# 02-ESP32.net
KiCad netlist of a schematic drawn in Altium Designer
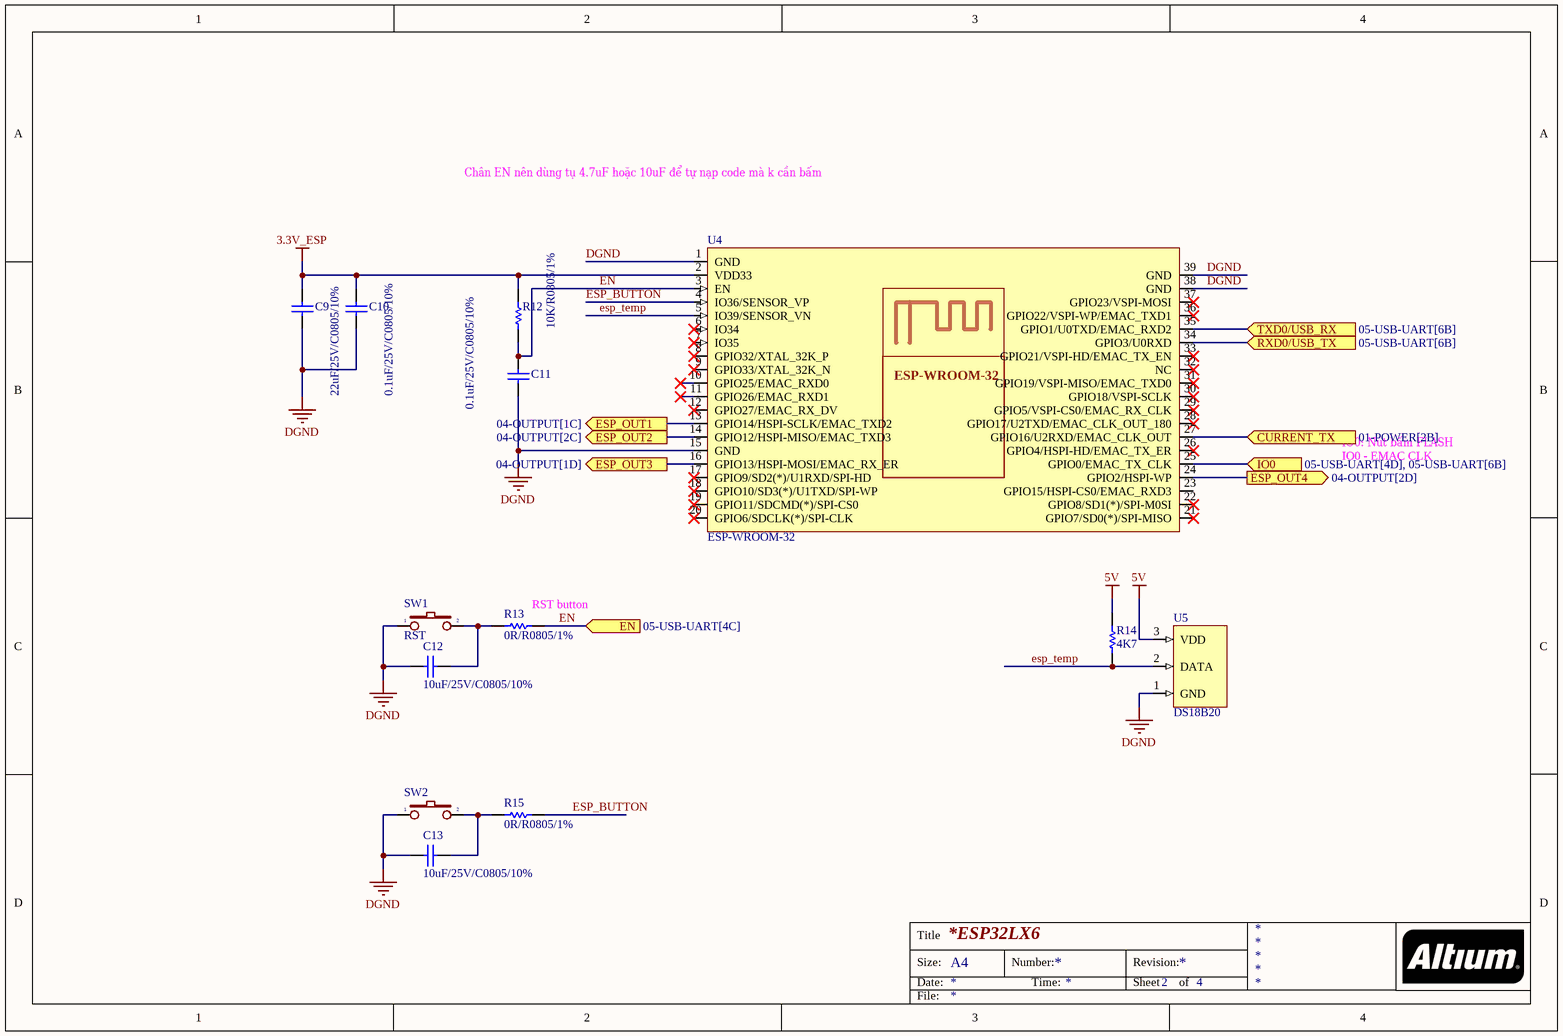
[diagram p0: 02-ESP32.SchDoc]

(export (version "E")
  (design (tool "Eeschema 10.0.6"))
  (components
    (comp (ref "C9")
      (value "22uF/25V/C0805/10%")
      (footprint "CAP_CERA_C2012(CC0805INCH)")
      (description "22µF ±20% 25V Ceramic Capacitor X5R 0805 (2012 Metric)")
      (fields (field (name "MANUFACTURER") "Tariff Applied"))
      (libsource (lib "GSHT_181013") (part "0.1uF/50V/C0603/10%"))
    )
    (comp (ref "C10")
      (value "0.1uF/25V/C0805/10%")
      (footprint "CAP_CERA_C2012(CC0805INCH)")
      (description "0.1µF ±10% 25V Ceramic Capacitor X7R 0805 (2012 Metric)")
      (libsource (lib "GSHT_181013") (part "0.1uF/50V/C0603/10%"))
    )
    (comp (ref "C11")
      (value "0.1uF/25V/C0805/10%")
      (footprint "CAP_CERA_C2012(CC0805INCH)")
      (description "0.1µF ±10% 25V Ceramic Capacitor X7R 0805 (2012 Metric)")
      (libsource (lib "GSHT_181013") (part "0.1uF/50V/C0603/10%"))
    )
    (comp (ref "C12")
      (value "10uF/25V/C0805/10%")
      (footprint "CAP_CERA_C2012(CC0805INCH)")
      (description "0.1µF ±10% 25V Ceramic Capacitor X7R 0805 (2012 Metric)")
      (libsource (lib "GSHT_181013") (part "0.1uF/50V/C0603/10%"))
    )
    (comp (ref "C13")
      (value "10uF/25V/C0805/10%")
      (footprint "CAP_CERA_C2012(CC0805INCH)")
      (description "0.1µF ±10% 25V Ceramic Capacitor X7R 0805 (2012 Metric)")
      (libsource (lib "GSHT_181013") (part "0.1uF/50V/C0603/10%"))
    )
    (comp (ref "R12")
      (value "10K/R0805/1%")
      (footprint "Res 0805 SMD")
      (description "10 kOhms ±1% 0.125W, 1/8W Chip Resistor 0805 (2012 Metric) Thick Film")
      (libsource (lib "GSHT_181013") (part "200K/R0603/1%"))
    )
    (comp (ref "R13")
      (value "0R/R0805/1%")
      (footprint "Res 0805 SMD")
      (description "0 Ohms Jumper 0.125W, 1/8W Chip Resistor 0805 (2012 Metric) Automotive AEC-Q200 Thick Film")
      (libsource (lib "GSHT_181013") (part "200K/R0603/1%"))
    )
    (comp (ref "R14")
      (value "4K7")
      (footprint "Res 0805 SMD")
      (description "4k7 Ohms Jumper 0.125W, 1/8W Chip Resistor 0805 (2012 Metric)")
      (libsource (lib "GSHT_181013") (part "200K/R0603/1%"))
    )
    (comp (ref "R15")
      (value "0R/R0805/1%")
      (footprint "Res 0805 SMD")
      (description "0 Ohms Jumper 0.125W, 1/8W Chip Resistor 0805 (2012 Metric) Automotive AEC-Q200 Thick Film")
      (libsource (lib "GSHT_181013") (part "200K/R0603/1%"))
    )
    (comp (ref "SW1")
      (value "RST")
      (footprint "Button 3x4mm")
      (description "SWITCH TACTILE SPST-NO 0.05A 12V")
      (libsource (lib "lpson") (part "SW2"))
    )
    (comp (ref "SW2")
      (value "RST")
      (footprint "Button 3x4mm")
      (description "SWITCH TACTILE SPST-NO 0.05A 12V")
      (libsource (lib "lpson") (part "SW2"))
    )
    (comp (ref "U4")
      (value "ESP-WROOM-32")
      (footprint "ESP32 WROOM")
      (description "ESP-WROOM-32 (8MB), WIFI MODULE 64 MBITS SPI FLASH")
      (libsource (lib "lpson") (part "ESP-WROOM-32"))
    )
    (comp (ref "U5") (value "DS18B20") (footprint "P2N2222AG") (libsource (lib "Schlib1") (part "DS18B20")))
  )
  (nets
    (net (code "1") (name "/CURRENT_TX") (class "Default")
      (node (ref "U4") (pin "27") (pinfunction "GPIO16/U2RXD/EMAC_CLK_OUT_27") (pintype "passive"))
    )
    (net (code "2") (name "/EN") (class "Default")
      (node (ref "C11") (pin "2") (pinfunction "2_2") (pintype "passive"))
      (node (ref "R12") (pin "2") (pinfunction "2_2") (pintype "passive"))
      (node (ref "R13") (pin "2") (pinfunction "2_2") (pintype "passive"))
      (node (ref "U4") (pin "3") (pinfunction "EN_3") (pintype "input"))
    )
    (net (code "3") (name "/ESP_BUTTON") (class "Default")
      (node (ref "R15") (pin "2") (pinfunction "2_2") (pintype "passive"))
      (node (ref "U4") (pin "4") (pinfunction "IO36/SENSOR_VP_4") (pintype "input"))
    )
    (net (code "4") (name "/ESP_OUT1") (class "Default")
      (node (ref "U4") (pin "13") (pinfunction "GPIO14/HSPI-SCLK/EMAC_TXD2_13") (pintype "passive"))
    )
    (net (code "5") (name "/ESP_OUT2") (class "Default")
      (node (ref "U4") (pin "14") (pinfunction "GPIO12/HSPI-MISO/EMAC_TXD3_14") (pintype "passive"))
    )
    (net (code "6") (name "/ESP_OUT3") (class "Default")
      (node (ref "U4") (pin "16") (pinfunction "GPIO13/HSPI-MOSI/EMAC_RX_ER_16") (pintype "passive"))
    )
    (net (code "7") (name "/ESP_OUT4") (class "Default")
      (node (ref "U4") (pin "24") (pinfunction "GPIO2/HSPI-WP_24") (pintype "passive"))
    )
    (net (code "8") (name "/IO0") (class "Default")
      (node (ref "U4") (pin "25") (pinfunction "GPIO0/EMAC_TX_CLK_25") (pintype "passive"))
    )
    (net (code "9") (name "/RXD0{slash}USB_TX") (class "Default")
      (node (ref "U4") (pin "34") (pinfunction "GPIO3/U0RXD_34") (pintype "passive"))
    )
    (net (code "10") (name "/TXD0{slash}USB_RX") (class "Default")
      (node (ref "U4") (pin "35") (pinfunction "GPIO1/U0TXD/EMAC_RXD2_35") (pintype "passive"))
    )
    (net (code "11") (name "/esp_temp") (class "Default")
      (node (ref "R14") (pin "1") (pinfunction "1_1") (pintype "passive"))
      (node (ref "U4") (pin "5") (pinfunction "IO39/SENSOR_VN_5") (pintype "input"))
      (node (ref "U5") (pin "2") (pinfunction "DATA_2") (pintype "input"))
    )
    (net (code "12") (name "3.3V_ESP") (class "Default")
      (node (ref "C10") (pin "2") (pinfunction "2_2") (pintype "passive"))
      (node (ref "C9") (pin "2") (pinfunction "2_2") (pintype "passive"))
      (node (ref "R12") (pin "1") (pinfunction "1_1") (pintype "passive"))
      (node (ref "U4") (pin "2") (pinfunction "VDD33_2") (pintype "passive"))
    )
    (net (code "13") (name "5V") (class "Default")
      (node (ref "R14") (pin "2") (pinfunction "2_2") (pintype "passive"))
      (node (ref "U5") (pin "3") (pinfunction "VDD_3") (pintype "input"))
    )
    (net (code "14") (name "DGND") (class "Default")
      (node (ref "C10") (pin "1") (pinfunction "1_1") (pintype "passive"))
      (node (ref "C11") (pin "1") (pinfunction "1_1") (pintype "passive"))
      (node (ref "C12") (pin "2") (pinfunction "2_2") (pintype "passive"))
      (node (ref "C13") (pin "2") (pinfunction "2_2") (pintype "passive"))
      (node (ref "C9") (pin "1") (pinfunction "1_1") (pintype "passive"))
      (node (ref "SW1") (pin "1") (pinfunction "1_1") (pintype "passive"))
      (node (ref "SW2") (pin "1") (pinfunction "1_1") (pintype "passive"))
      (node (ref "U4") (pin "1") (pinfunction "GND_1") (pintype "passive"))
      (node (ref "U4") (pin "15") (pinfunction "GND_15") (pintype "passive"))
      (node (ref "U4") (pin "38") (pinfunction "GND_38") (pintype "passive"))
      (node (ref "U4") (pin "39") (pinfunction "GND_39") (pintype "passive"))
      (node (ref "U5") (pin "1") (pinfunction "GND_1") (pintype "input"))
    )
    (net (code "15") (name "Net-(C12-Pad1)") (class "Default")
      (node (ref "C12") (pin "1") (pinfunction "1_1") (pintype "passive"))
      (node (ref "R13") (pin "1") (pinfunction "1_1") (pintype "passive"))
      (node (ref "SW1") (pin "2") (pinfunction "2_2") (pintype "passive"))
    )
    (net (code "16") (name "Net-(C13-Pad1)") (class "Default")
      (node (ref "C13") (pin "1") (pinfunction "1_1") (pintype "passive"))
      (node (ref "R15") (pin "1") (pinfunction "1_1") (pintype "passive"))
      (node (ref "SW2") (pin "2") (pinfunction "2_2") (pintype "passive"))
    )
    (net (code "17") (name "unconnected-(U4-GPIO4{slash}HSPI-HD{slash}EMAC_TX_ER-Pad26)") (class "Default")
      (node (ref "U4") (pin "26") (pinfunction "GPIO4/HSPI-HD/EMAC_TX_ER_26") (pintype "passive+no_connect"))
    )
    (net (code "18") (name "unconnected-(U4-GPIO5{slash}VSPI-CS0{slash}EMAC_RX_CLK-Pad29)") (class "Default")
      (node (ref "U4") (pin "29") (pinfunction "GPIO5/VSPI-CS0/EMAC_RX_CLK_29") (pintype "passive+no_connect"))
    )
    (net (code "19") (name "unconnected-(U4-GPIO6{slash}SDCLK(*){slash}SPI-CLK-Pad20)") (class "Default")
      (node (ref "U4") (pin "20") (pinfunction "GPIO6/SDCLK(*)/SPI-CLK_20") (pintype "passive+no_connect"))
    )
    (net (code "20") (name "unconnected-(U4-GPIO7{slash}SD0(*){slash}SPI-MISO-Pad21)") (class "Default")
      (node (ref "U4") (pin "21") (pinfunction "GPIO7/SD0(*)/SPI-MISO_21") (pintype "passive+no_connect"))
    )
    (net (code "21") (name "unconnected-(U4-GPIO8{slash}SD1(*){slash}SPI-M0SI-Pad22)") (class "Default")
      (node (ref "U4") (pin "22") (pinfunction "GPIO8/SD1(*)/SPI-M0SI_22") (pintype "passive+no_connect"))
    )
    (net (code "22") (name "unconnected-(U4-GPIO9{slash}SD2(*){slash}U1RXD{slash}SPI-HD-Pad17)") (class "Default")
      (node (ref "U4") (pin "17") (pinfunction "GPIO9/SD2(*)/U1RXD/SPI-HD_17") (pintype "passive+no_connect"))
    )
    (net (code "23") (name "unconnected-(U4-GPIO10{slash}SD3(*){slash}U1TXD{slash}SPI-WP-Pad18)") (class "Default")
      (node (ref "U4") (pin "18") (pinfunction "GPIO10/SD3(*)/U1TXD/SPI-WP_18") (pintype "passive+no_connect"))
    )
    (net (code "24") (name "unconnected-(U4-GPIO11{slash}SDCMD(*){slash}SPI-CS0-Pad19)") (class "Default")
      (node (ref "U4") (pin "19") (pinfunction "GPIO11/SDCMD(*)/SPI-CS0_19") (pintype "passive+no_connect"))
    )
    (net (code "25") (name "unconnected-(U4-GPIO15{slash}HSPI-CS0{slash}EMAC_RXD3-Pad23)") (class "Default")
      (node (ref "U4") (pin "23") (pinfunction "GPIO15/HSPI-CS0/EMAC_RXD3_23") (pintype "passive"))
    )
    (net (code "26") (name "unconnected-(U4-GPIO17{slash}U2TXD{slash}EMAC_CLK_OUT_180-Pad28)") (class "Default")
      (node (ref "U4") (pin "28") (pinfunction "GPIO17/U2TXD/EMAC_CLK_OUT_180_28") (pintype "passive+no_connect"))
    )
    (net (code "27") (name "unconnected-(U4-GPIO18{slash}VSPI-SCLK-Pad30)") (class "Default")
      (node (ref "U4") (pin "30") (pinfunction "GPIO18/VSPI-SCLK_30") (pintype "passive+no_connect"))
    )
    (net (code "28") (name "unconnected-(U4-GPIO19{slash}VSPI-MISO{slash}EMAC_TXD0-Pad31)") (class "Default")
      (node (ref "U4") (pin "31") (pinfunction "GPIO19/VSPI-MISO/EMAC_TXD0_31") (pintype "passive+no_connect"))
    )
    (net (code "29") (name "unconnected-(U4-GPIO21{slash}VSPI-HD{slash}EMAC_TX_EN-Pad33)") (class "Default")
      (node (ref "U4") (pin "33") (pinfunction "GPIO21/VSPI-HD/EMAC_TX_EN_33") (pintype "passive+no_connect"))
    )
    (net (code "30") (name "unconnected-(U4-GPIO22{slash}VSPI-WP{slash}EMAC_TXD1-Pad36)") (class "Default")
      (node (ref "U4") (pin "36") (pinfunction "GPIO22/VSPI-WP/EMAC_TXD1_36") (pintype "passive+no_connect"))
    )
    (net (code "31") (name "unconnected-(U4-GPIO23{slash}VSPI-MOSI-Pad37)") (class "Default")
      (node (ref "U4") (pin "37") (pinfunction "GPIO23/VSPI-MOSI_37") (pintype "passive+no_connect"))
    )
    (net (code "32") (name "unconnected-(U4-GPIO25{slash}EMAC_RXD0-Pad10)") (class "Default")
      (node (ref "U4") (pin "10") (pinfunction "GPIO25/EMAC_RXD0_10") (pintype "passive+no_connect"))
    )
    (net (code "33") (name "unconnected-(U4-GPIO26{slash}EMAC_RXD1-Pad11)") (class "Default")
      (node (ref "U4") (pin "11") (pinfunction "GPIO26/EMAC_RXD1_11") (pintype "passive+no_connect"))
    )
    (net (code "34") (name "unconnected-(U4-GPIO27{slash}EMAC_RX_DV-Pad12)") (class "Default")
      (node (ref "U4") (pin "12") (pinfunction "GPIO27/EMAC_RX_DV_12") (pintype "passive+no_connect"))
    )
    (net (code "35") (name "unconnected-(U4-GPIO32{slash}XTAL_32K_P-Pad8)") (class "Default")
      (node (ref "U4") (pin "8") (pinfunction "GPIO32/XTAL_32K_P_8") (pintype "passive+no_connect"))
    )
    (net (code "36") (name "unconnected-(U4-GPIO33{slash}XTAL_32K_N-Pad9)") (class "Default")
      (node (ref "U4") (pin "9") (pinfunction "GPIO33/XTAL_32K_N_9") (pintype "passive+no_connect"))
    )
    (net (code "37") (name "unconnected-(U4-IO34-Pad6)") (class "Default")
      (node (ref "U4") (pin "6") (pinfunction "IO34_6") (pintype "input+no_connect"))
    )
    (net (code "38") (name "unconnected-(U4-IO35-Pad7)") (class "Default")
      (node (ref "U4") (pin "7") (pinfunction "IO35_7") (pintype "input+no_connect"))
    )
    (net (code "39") (name "unconnected-(U4-NC-Pad32)") (class "Default")
      (node (ref "U4") (pin "32") (pinfunction "NC_32") (pintype "passive+no_connect"))
    )
  )
)
